# SCH_OnboardRobot_2024-01-02.net
KiCad netlist of a schematic drawn in EasyEDA
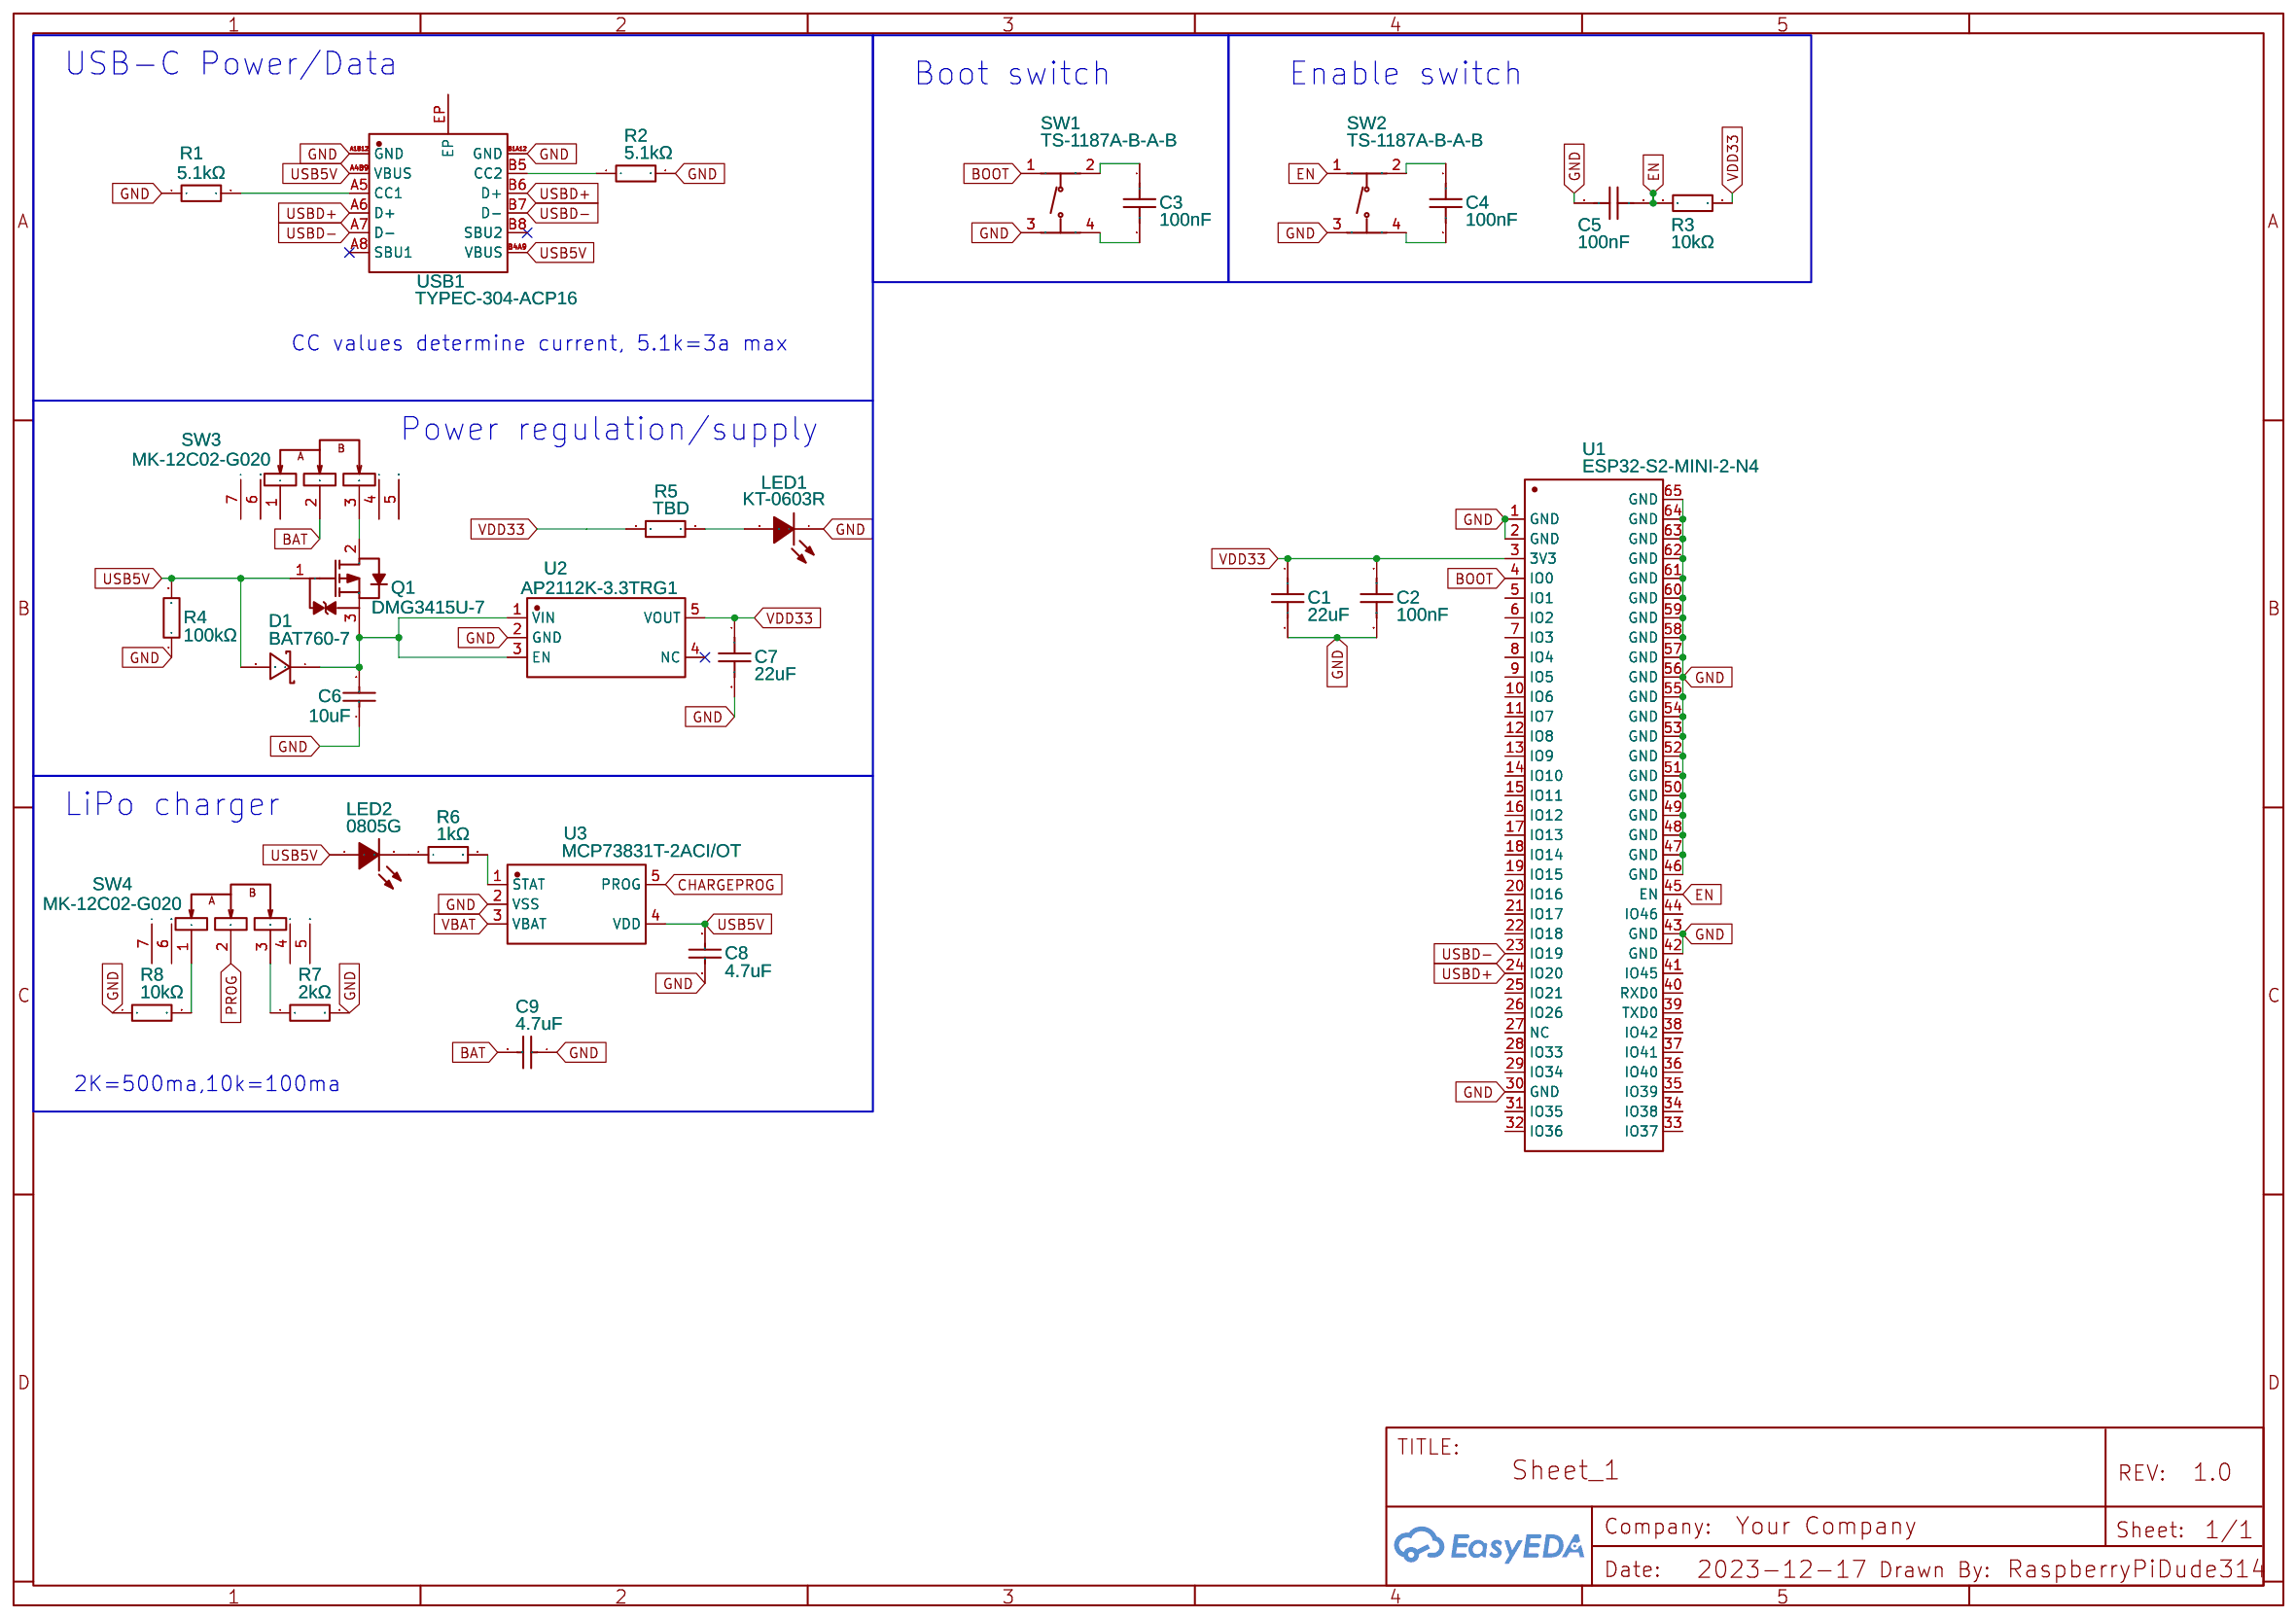
[diagram p0: schematic sheet]

(export (version "E")
  (design (tool "Eeschema 10.0.6"))
  (components
    (comp (ref "C1")
      (value "22uF")
      (fields
        (field (name "Manufacturer Part") "CL10A226MQ8NRNC")
        (field (name "Manufacturer") "SAMSUNG(三星)")
      )
      (libsource (lib "") (part "CL10A226MQ8NRNC"))
    )
    (comp (ref "C2")
      (value "100nF")
      (fields
        (field (name "Manufacturer Part") "CC0603KRX7R9BB104")
        (field (name "Manufacturer") "YAGEO(国巨)")
      )
      (libsource (lib "") (part "CC0603KRX7R9BB104_1"))
    )
    (comp (ref "C3")
      (value "100nF")
      (fields
        (field (name "Manufacturer Part") "CC0603KRX7R9BB104")
        (field (name "Manufacturer") "YAGEO(国巨)")
      )
      (libsource (lib "") (part "CC0603KRX7R9BB104_1"))
    )
    (comp (ref "C4")
      (value "100nF")
      (fields
        (field (name "Manufacturer Part") "CC0603KRX7R9BB104")
        (field (name "Manufacturer") "YAGEO(国巨)")
      )
      (libsource (lib "") (part "CC0603KRX7R9BB104_1"))
    )
    (comp (ref "C5")
      (value "100nF")
      (fields
        (field (name "Manufacturer Part") "CC0603KRX7R9BB104")
        (field (name "Manufacturer") "YAGEO(国巨)")
      )
      (libsource (lib "") (part "CC0603KRX7R9BB104"))
    )
    (comp (ref "C6")
      (value "10uF")
      (fields
        (field (name "Manufacturer Part") "CL21A106KAYNNNE")
        (field (name "Manufacturer") "SAMSUNG(三星)")
      )
      (libsource (lib "") (part "CL21A106KAYNNNE"))
    )
    (comp (ref "C7")
      (value "22uF")
      (fields
        (field (name "Manufacturer Part") "CL10A226MQ8NRNC")
        (field (name "Manufacturer") "SAMSUNG(三星)")
      )
      (libsource (lib "") (part "CL10A226MQ8NRNC"))
    )
    (comp (ref "C8")
      (value "4.7uF")
      (fields
        (field (name "Manufacturer Part") "CL05A475MP5NRNC")
        (field (name "Manufacturer") "SAMSUNG(三星)")
      )
      (libsource (lib "") (part "CL05A475MP5NRNC_1"))
    )
    (comp (ref "C9")
      (value "4.7uF")
      (fields
        (field (name "Manufacturer Part") "CL05A475MP5NRNC")
        (field (name "Manufacturer") "SAMSUNG(三星)")
      )
      (libsource (lib "") (part "CL05A475MP5NRNC"))
    )
    (comp (ref "D1")
      (value "BAT760-7")
      (fields (field (name "Manufacturer") "DIODES(美台)"))
      (libsource (lib "") (part "BAT760-7"))
    )
    (comp (ref "LED1")
      (value "KT-0603R")
      (fields (field (name "Manufacturer") "KENTO"))
      (libsource (lib "") (part "KT-0603R"))
    )
    (comp (ref "LED2")
      (value "0805G")
      (fields (field (name "Manufacturer Part") "KT-0805翠绿") (field (name "Manufacturer") "KENTO"))
      (libsource (lib "") (part "0805G (Green)"))
    )
    (comp (ref "Q1")
      (value "DMG3415U-7")
      (fields (field (name "Manufacturer") "DIODES(美台)"))
      (libsource (lib "") (part "DMG3415U-7"))
    )
    (comp (ref "R1")
      (value "5.1kΩ")
      (fields
        (field (name "Manufacturer Part") "0402WGF5101TCE")
        (field (name "Manufacturer") "UNI-ROYAL(厚声)")
      )
      (libsource (lib "") (part "0402WGF5101TCE"))
    )
    (comp (ref "R2")
      (value "5.1kΩ")
      (fields
        (field (name "Manufacturer Part") "0402WGF5101TCE")
        (field (name "Manufacturer") "UNI-ROYAL(厚声)")
      )
      (libsource (lib "") (part "0402WGF5101TCE"))
    )
    (comp (ref "R3")
      (value "10kΩ")
      (fields
        (field (name "Manufacturer Part") "0603WAF1002T5E")
        (field (name "Manufacturer") "UNI-ROYAL(厚声)")
      )
      (libsource (lib "") (part "0603WAF1002T5E"))
    )
    (comp (ref "R4")
      (value "100kΩ")
      (fields
        (field (name "Manufacturer Part") "1206W4F1003T5E")
        (field (name "Manufacturer") "UNI-ROYAL(厚声)")
      )
      (libsource (lib "") (part "1206W4F1003T5E"))
    )
    (comp (ref "R5") (value "TBD") (libsource (lib "") (part "0805 360 ohm Resistor")))
    (comp (ref "R6")
      (value "1kΩ")
      (fields
        (field (name "Manufacturer Part") "0805W8F1001T5E")
        (field (name "Manufacturer") "UNI-ROYAL(厚声)")
      )
      (libsource (lib "") (part "0805W8F1001T5E"))
    )
    (comp (ref "R7")
      (value "2kΩ")
      (fields
        (field (name "Manufacturer Part") "0603WAF2001T5E")
        (field (name "Manufacturer") "UNI-ROYAL(厚声)")
      )
      (libsource (lib "") (part "0603WAF2001T5E"))
    )
    (comp (ref "R8")
      (value "10kΩ")
      (fields
        (field (name "Manufacturer Part") "0805W8F1002T5E")
        (field (name "Manufacturer") "UNI-ROYAL(厚声)")
      )
      (libsource (lib "") (part "0805W8F1002T5E"))
    )
    (comp (ref "SW1")
      (value "TS-1187A-B-A-B")
      (fields (field (name "Manufacturer") "XKB Connectivity(中国星坤)"))
      (libsource (lib "") (part "TS-1187A-B-A-B"))
    )
    (comp (ref "SW2")
      (value "TS-1187A-B-A-B")
      (fields (field (name "Manufacturer") "XKB Connectivity(中国星坤)"))
      (libsource (lib "") (part "TS-1187A-B-A-B"))
    )
    (comp (ref "SW3")
      (value "MK-12C02-G020")
      (fields (field (name "Manufacturer") "G-Switch"))
      (libsource (lib "") (part "MK-12C02-G020"))
    )
    (comp (ref "SW4")
      (value "MK-12C02-G020")
      (fields (field (name "Manufacturer") "G-Switch"))
      (libsource (lib "") (part "MK-12C02-G020"))
    )
    (comp (ref "U1")
      (value "ESP32-S2-MINI-2-N4")
      (fields (field (name "Manufacturer") "ESPRESSIF(乐鑫)"))
      (libsource (lib "") (part "ESP32-S2-MINI-2-N4"))
    )
    (comp (ref "U2")
      (value "AP2112K-3.3TRG1")
      (fields (field (name "Manufacturer") "DIODES(美台)"))
      (libsource (lib "") (part "AP2112K-3.3TRG1"))
    )
    (comp (ref "U3")
      (value "MCP73831T-2ACI/OT")
      (fields (field (name "Manufacturer") "MICROCHIP(美国微芯)"))
      (libsource (lib "") (part "MCP73831T-2ACI/OT"))
    )
    (comp (ref "USB1")
      (value "TYPEC-304-ACP16")
      (fields (field (name "Manufacturer") "XUNPU(讯普)"))
      (libsource (lib "") (part "TYPEC-304-ACP16"))
    )
  )
  (nets
    (net (code "1") (name "BAT") (class "Default")
      (node (ref "C9") (pin "2") (pinfunction "2_2") (pintype "input"))
      (node (ref "SW3") (pin "2") (pinfunction "2_2") (pintype "unspecified"))
    )
    (net (code "2") (name "BOOT") (class "Default")
      (node (ref "SW1") (pin "1") (pinfunction "A_1") (pintype "unspecified"))
      (node (ref "U1") (pin "4") (pinfunction "IO0_4") (pintype "unspecified"))
    )
    (net (code "3") (name "CHARGEPROG") (class "Default")
      (node (ref "U3") (pin "5") (pinfunction "PROG_5") (pintype "unspecified"))
    )
    (net (code "4") (name "EN") (class "Default")
      (node (ref "C5") (pin "2") (pinfunction "2_2") (pintype "unspecified"))
      (node (ref "R3") (pin "2") (pinfunction "2_2") (pintype "input"))
      (node (ref "SW2") (pin "1") (pinfunction "A_1") (pintype "unspecified"))
      (node (ref "U1") (pin "45") (pinfunction "EN_45") (pintype "unspecified"))
    )
    (net (code "5") (name "GND") (class "Default")
      (node (ref "C1") (pin "2") (pinfunction "2_2") (pintype "unspecified"))
      (node (ref "C2") (pin "2") (pinfunction "2_2") (pintype "unspecified"))
      (node (ref "C5") (pin "1") (pinfunction "1_1") (pintype "unspecified"))
      (node (ref "C6") (pin "1") (pinfunction "1_1") (pintype "input"))
      (node (ref "C7") (pin "2") (pinfunction "2_2") (pintype "unspecified"))
      (node (ref "C8") (pin "1") (pinfunction "1_1") (pintype "input"))
      (node (ref "C9") (pin "1") (pinfunction "1_1") (pintype "input"))
      (node (ref "LED1") (pin "1") (pinfunction "K_1") (pintype "unspecified"))
      (node (ref "R1") (pin "1") (pinfunction "1_1") (pintype "input"))
      (node (ref "R2") (pin "2") (pinfunction "2_2") (pintype "input"))
      (node (ref "R4") (pin "1") (pinfunction "1_1") (pintype "input"))
      (node (ref "R7") (pin "2") (pinfunction "2_2") (pintype "input"))
      (node (ref "R8") (pin "1") (pinfunction "1_1") (pintype "input"))
      (node (ref "SW1") (pin "3") (pinfunction "C_3") (pintype "unspecified"))
      (node (ref "SW2") (pin "3") (pinfunction "C_3") (pintype "unspecified"))
      (node (ref "U1") (pin "1") (pinfunction "GND_1") (pintype "unspecified"))
      (node (ref "U1") (pin "2") (pinfunction "GND_2") (pintype "unspecified"))
      (node (ref "U1") (pin "30") (pinfunction "GND_30") (pintype "unspecified"))
      (node (ref "U1") (pin "42") (pinfunction "GND_42") (pintype "unspecified"))
      (node (ref "U1") (pin "43") (pinfunction "GND_43") (pintype "unspecified"))
      (node (ref "U1") (pin "46") (pinfunction "GND_46") (pintype "unspecified"))
      (node (ref "U1") (pin "47") (pinfunction "GND_47") (pintype "unspecified"))
      (node (ref "U1") (pin "48") (pinfunction "GND_48") (pintype "unspecified"))
      (node (ref "U1") (pin "49") (pinfunction "GND_49") (pintype "unspecified"))
      (node (ref "U1") (pin "50") (pinfunction "GND_50") (pintype "unspecified"))
      (node (ref "U1") (pin "51") (pinfunction "GND_51") (pintype "unspecified"))
      (node (ref "U1") (pin "52") (pinfunction "GND_52") (pintype "unspecified"))
      (node (ref "U1") (pin "53") (pinfunction "GND_53") (pintype "unspecified"))
      (node (ref "U1") (pin "54") (pinfunction "GND_54") (pintype "unspecified"))
      (node (ref "U1") (pin "55") (pinfunction "GND_55") (pintype "unspecified"))
      (node (ref "U1") (pin "56") (pinfunction "GND_56") (pintype "unspecified"))
      (node (ref "U1") (pin "57") (pinfunction "GND_57") (pintype "unspecified"))
      (node (ref "U1") (pin "58") (pinfunction "GND_58") (pintype "unspecified"))
      (node (ref "U1") (pin "59") (pinfunction "GND_59") (pintype "unspecified"))
      (node (ref "U1") (pin "60") (pinfunction "GND_60") (pintype "unspecified"))
      (node (ref "U1") (pin "61") (pinfunction "GND_61") (pintype "unspecified"))
      (node (ref "U1") (pin "62") (pinfunction "GND_62") (pintype "unspecified"))
      (node (ref "U1") (pin "63") (pinfunction "GND_63") (pintype "unspecified"))
      (node (ref "U1") (pin "64") (pinfunction "GND_64") (pintype "unspecified"))
      (node (ref "U1") (pin "65") (pinfunction "GND_65") (pintype "unspecified"))
      (node (ref "U2") (pin "2") (pinfunction "GND_2") (pintype "unspecified"))
      (node (ref "U3") (pin "2") (pinfunction "VSS_2") (pintype "unspecified"))
      (node (ref "USB1") (pin "A1B12") (pinfunction "GND_A1B12") (pintype "unspecified"))
      (node (ref "USB1") (pin "B1A12") (pinfunction "GND_B1A12") (pintype "unspecified"))
    )
    (net (code "6") (name "Net-(LED1-A)") (class "Default")
      (node (ref "LED1") (pin "2") (pinfunction "A_2") (pintype "unspecified"))
      (node (ref "R5") (pin "2") (pinfunction "2_2") (pintype "unspecified"))
    )
    (net (code "7") (name "Net-(LED2-K)") (class "Default")
      (node (ref "LED2") (pin "2") (pinfunction "K_2") (pintype "unspecified"))
      (node (ref "R6") (pin "1") (pinfunction "1_1") (pintype "input"))
    )
    (net (code "8") (name "Net-(Q1-D)") (class "Default")
      (node (ref "Q1") (pin "2") (pinfunction "D_2") (pintype "unspecified"))
      (node (ref "SW3") (pin "3") (pinfunction "3_3") (pintype "unspecified"))
    )
    (net (code "9") (name "Net-(Q1-S)") (class "Default")
      (node (ref "C6") (pin "2") (pinfunction "2_2") (pintype "input"))
      (node (ref "D1") (pin "1") (pinfunction "1_1") (pintype "unspecified"))
      (node (ref "Q1") (pin "3") (pinfunction "S_3") (pintype "unspecified"))
      (node (ref "U2") (pin "1") (pinfunction "VIN_1") (pintype "unspecified"))
      (node (ref "U2") (pin "3") (pinfunction "EN_3") (pintype "unspecified"))
    )
    (net (code "10") (name "Net-(R7-Pad1)") (class "Default")
      (node (ref "R7") (pin "1") (pinfunction "1_1") (pintype "input"))
      (node (ref "SW4") (pin "3") (pinfunction "3_3") (pintype "unspecified"))
    )
    (net (code "11") (name "Net-(R8-Pad2)") (class "Default")
      (node (ref "R8") (pin "2") (pinfunction "2_2") (pintype "input"))
      (node (ref "SW4") (pin "1") (pinfunction "1_1") (pintype "unspecified"))
    )
    (net (code "12") (name "Net-(SW1-B)") (class "Default")
      (node (ref "C3") (pin "1") (pinfunction "1_1") (pintype "unspecified"))
      (node (ref "SW1") (pin "2") (pinfunction "B_2") (pintype "unspecified"))
    )
    (net (code "13") (name "Net-(SW1-D)") (class "Default")
      (node (ref "C3") (pin "2") (pinfunction "2_2") (pintype "unspecified"))
      (node (ref "SW1") (pin "4") (pinfunction "D_4") (pintype "unspecified"))
    )
    (net (code "14") (name "Net-(SW2-B)") (class "Default")
      (node (ref "C4") (pin "1") (pinfunction "1_1") (pintype "unspecified"))
      (node (ref "SW2") (pin "2") (pinfunction "B_2") (pintype "unspecified"))
    )
    (net (code "15") (name "Net-(SW2-D)") (class "Default")
      (node (ref "C4") (pin "2") (pinfunction "2_2") (pintype "unspecified"))
      (node (ref "SW2") (pin "4") (pinfunction "D_4") (pintype "unspecified"))
    )
    (net (code "16") (name "Net-(U3-STAT)") (class "Default")
      (node (ref "R6") (pin "2") (pinfunction "2_2") (pintype "input"))
      (node (ref "U3") (pin "1") (pinfunction "STAT_1") (pintype "unspecified"))
    )
    (net (code "17") (name "Net-(USB1-CC1)") (class "Default")
      (node (ref "R1") (pin "2") (pinfunction "2_2") (pintype "input"))
      (node (ref "USB1") (pin "A5") (pinfunction "CC1_A5") (pintype "unspecified"))
    )
    (net (code "18") (name "Net-(USB1-CC2)") (class "Default")
      (node (ref "R2") (pin "1") (pinfunction "1_1") (pintype "input"))
      (node (ref "USB1") (pin "B5") (pinfunction "CC2_B5") (pintype "unspecified"))
    )
    (net (code "19") (name "PROG") (class "Default")
      (node (ref "SW4") (pin "2") (pinfunction "2_2") (pintype "unspecified"))
    )
    (net (code "20") (name "USB5V") (class "Default")
      (node (ref "C8") (pin "2") (pinfunction "2_2") (pintype "input"))
      (node (ref "D1") (pin "2") (pinfunction "2_2") (pintype "unspecified"))
      (node (ref "LED2") (pin "1") (pinfunction "A_1") (pintype "unspecified"))
      (node (ref "Q1") (pin "1") (pinfunction "G_1") (pintype "unspecified"))
      (node (ref "R4") (pin "2") (pinfunction "2_2") (pintype "input"))
      (node (ref "U3") (pin "4") (pinfunction "VDD_4") (pintype "unspecified"))
      (node (ref "USB1") (pin "A4B9") (pinfunction "VBUS_A4B9") (pintype "unspecified"))
      (node (ref "USB1") (pin "B4A9") (pinfunction "VBUS_B4A9") (pintype "unspecified"))
    )
    (net (code "21") (name "USBD+") (class "Default")
      (node (ref "U1") (pin "24") (pinfunction "IO20_24") (pintype "unspecified"))
      (node (ref "USB1") (pin "A6") (pinfunction "D+_A6") (pintype "unspecified"))
      (node (ref "USB1") (pin "B6") (pinfunction "D+_B6") (pintype "unspecified"))
    )
    (net (code "22") (name "USBD-") (class "Default")
      (node (ref "U1") (pin "23") (pinfunction "IO19_23") (pintype "unspecified"))
      (node (ref "USB1") (pin "A7") (pinfunction "D-_A7") (pintype "unspecified"))
      (node (ref "USB1") (pin "B7") (pinfunction "D-_B7") (pintype "unspecified"))
    )
    (net (code "23") (name "VBAT") (class "Default")
      (node (ref "U3") (pin "3") (pinfunction "VBAT_3") (pintype "unspecified"))
    )
    (net (code "24") (name "VDD33") (class "Default")
      (node (ref "C1") (pin "1") (pinfunction "1_1") (pintype "unspecified"))
      (node (ref "C2") (pin "1") (pinfunction "1_1") (pintype "unspecified"))
      (node (ref "C7") (pin "1") (pinfunction "1_1") (pintype "unspecified"))
      (node (ref "R3") (pin "1") (pinfunction "1_1") (pintype "input"))
      (node (ref "R5") (pin "1") (pinfunction "1_1") (pintype "unspecified"))
      (node (ref "U1") (pin "3") (pinfunction "3V3_3") (pintype "unspecified"))
      (node (ref "U2") (pin "5") (pinfunction "VOUT_5") (pintype "unspecified"))
    )
    (net (code "25") (name "unconnected-(SW3-Pad1)") (class "Default")
      (node (ref "SW3") (pin "1") (pinfunction "1_1") (pintype "unspecified"))
    )
    (net (code "26") (name "unconnected-(SW3-Pad4)") (class "Default")
      (node (ref "SW3") (pin "4") (pinfunction "4_4") (pintype "unspecified"))
    )
    (net (code "27") (name "unconnected-(SW3-Pad5)") (class "Default")
      (node (ref "SW3") (pin "5") (pinfunction "5_5") (pintype "unspecified"))
    )
    (net (code "28") (name "unconnected-(SW3-Pad6)") (class "Default")
      (node (ref "SW3") (pin "6") (pinfunction "6_6") (pintype "unspecified"))
    )
    (net (code "29") (name "unconnected-(SW3-Pad7)") (class "Default")
      (node (ref "SW3") (pin "7") (pinfunction "7_7") (pintype "unspecified"))
    )
    (net (code "30") (name "unconnected-(SW4-Pad4)") (class "Default")
      (node (ref "SW4") (pin "4") (pinfunction "4_4") (pintype "unspecified"))
    )
    (net (code "31") (name "unconnected-(SW4-Pad5)") (class "Default")
      (node (ref "SW4") (pin "5") (pinfunction "5_5") (pintype "unspecified"))
    )
    (net (code "32") (name "unconnected-(SW4-Pad6)") (class "Default")
      (node (ref "SW4") (pin "6") (pinfunction "6_6") (pintype "unspecified"))
    )
    (net (code "33") (name "unconnected-(SW4-Pad7)") (class "Default")
      (node (ref "SW4") (pin "7") (pinfunction "7_7") (pintype "unspecified"))
    )
    (net (code "34") (name "unconnected-(U1-IO1-Pad5)") (class "Default")
      (node (ref "U1") (pin "5") (pinfunction "IO1_5") (pintype "unspecified"))
    )
    (net (code "35") (name "unconnected-(U1-IO2-Pad6)") (class "Default")
      (node (ref "U1") (pin "6") (pinfunction "IO2_6") (pintype "unspecified"))
    )
    (net (code "36") (name "unconnected-(U1-IO3-Pad7)") (class "Default")
      (node (ref "U1") (pin "7") (pinfunction "IO3_7") (pintype "unspecified"))
    )
    (net (code "37") (name "unconnected-(U1-IO4-Pad8)") (class "Default")
      (node (ref "U1") (pin "8") (pinfunction "IO4_8") (pintype "unspecified"))
    )
    (net (code "38") (name "unconnected-(U1-IO5-Pad9)") (class "Default")
      (node (ref "U1") (pin "9") (pinfunction "IO5_9") (pintype "unspecified"))
    )
    (net (code "39") (name "unconnected-(U1-IO6-Pad10)") (class "Default")
      (node (ref "U1") (pin "10") (pinfunction "IO6_10") (pintype "unspecified"))
    )
    (net (code "40") (name "unconnected-(U1-IO7-Pad11)") (class "Default")
      (node (ref "U1") (pin "11") (pinfunction "IO7_11") (pintype "unspecified"))
    )
    (net (code "41") (name "unconnected-(U1-IO8-Pad12)") (class "Default")
      (node (ref "U1") (pin "12") (pinfunction "IO8_12") (pintype "unspecified"))
    )
    (net (code "42") (name "unconnected-(U1-IO9-Pad13)") (class "Default")
      (node (ref "U1") (pin "13") (pinfunction "IO9_13") (pintype "unspecified"))
    )
    (net (code "43") (name "unconnected-(U1-IO10-Pad14)") (class "Default")
      (node (ref "U1") (pin "14") (pinfunction "IO10_14") (pintype "unspecified"))
    )
    (net (code "44") (name "unconnected-(U1-IO11-Pad15)") (class "Default")
      (node (ref "U1") (pin "15") (pinfunction "IO11_15") (pintype "unspecified"))
    )
    (net (code "45") (name "unconnected-(U1-IO12-Pad16)") (class "Default")
      (node (ref "U1") (pin "16") (pinfunction "IO12_16") (pintype "unspecified"))
    )
    (net (code "46") (name "unconnected-(U1-IO13-Pad17)") (class "Default")
      (node (ref "U1") (pin "17") (pinfunction "IO13_17") (pintype "unspecified"))
    )
    (net (code "47") (name "unconnected-(U1-IO14-Pad18)") (class "Default")
      (node (ref "U1") (pin "18") (pinfunction "IO14_18") (pintype "unspecified"))
    )
    (net (code "48") (name "unconnected-(U1-IO15-Pad19)") (class "Default")
      (node (ref "U1") (pin "19") (pinfunction "IO15_19") (pintype "unspecified"))
    )
    (net (code "49") (name "unconnected-(U1-IO16-Pad20)") (class "Default")
      (node (ref "U1") (pin "20") (pinfunction "IO16_20") (pintype "unspecified"))
    )
    (net (code "50") (name "unconnected-(U1-IO17-Pad21)") (class "Default")
      (node (ref "U1") (pin "21") (pinfunction "IO17_21") (pintype "unspecified"))
    )
    (net (code "51") (name "unconnected-(U1-IO18-Pad22)") (class "Default")
      (node (ref "U1") (pin "22") (pinfunction "IO18_22") (pintype "unspecified"))
    )
    (net (code "52") (name "unconnected-(U1-IO21-Pad25)") (class "Default")
      (node (ref "U1") (pin "25") (pinfunction "IO21_25") (pintype "unspecified"))
    )
    (net (code "53") (name "unconnected-(U1-IO26-Pad26)") (class "Default")
      (node (ref "U1") (pin "26") (pinfunction "IO26_26") (pintype "unspecified"))
    )
    (net (code "54") (name "unconnected-(U1-IO33-Pad28)") (class "Default")
      (node (ref "U1") (pin "28") (pinfunction "IO33_28") (pintype "unspecified"))
    )
    (net (code "55") (name "unconnected-(U1-IO34-Pad29)") (class "Default")
      (node (ref "U1") (pin "29") (pinfunction "IO34_29") (pintype "unspecified"))
    )
    (net (code "56") (name "unconnected-(U1-IO35-Pad31)") (class "Default")
      (node (ref "U1") (pin "31") (pinfunction "IO35_31") (pintype "unspecified"))
    )
    (net (code "57") (name "unconnected-(U1-IO36-Pad32)") (class "Default")
      (node (ref "U1") (pin "32") (pinfunction "IO36_32") (pintype "unspecified"))
    )
    (net (code "58") (name "unconnected-(U1-IO37-Pad33)") (class "Default")
      (node (ref "U1") (pin "33") (pinfunction "IO37_33") (pintype "unspecified"))
    )
    (net (code "59") (name "unconnected-(U1-IO38-Pad34)") (class "Default")
      (node (ref "U1") (pin "34") (pinfunction "IO38_34") (pintype "unspecified"))
    )
    (net (code "60") (name "unconnected-(U1-IO39-Pad35)") (class "Default")
      (node (ref "U1") (pin "35") (pinfunction "IO39_35") (pintype "unspecified"))
    )
    (net (code "61") (name "unconnected-(U1-IO40-Pad36)") (class "Default")
      (node (ref "U1") (pin "36") (pinfunction "IO40_36") (pintype "unspecified"))
    )
    (net (code "62") (name "unconnected-(U1-IO41-Pad37)") (class "Default")
      (node (ref "U1") (pin "37") (pinfunction "IO41_37") (pintype "unspecified"))
    )
    (net (code "63") (name "unconnected-(U1-IO42-Pad38)") (class "Default")
      (node (ref "U1") (pin "38") (pinfunction "IO42_38") (pintype "unspecified"))
    )
    (net (code "64") (name "unconnected-(U1-IO45-Pad41)") (class "Default")
      (node (ref "U1") (pin "41") (pinfunction "IO45_41") (pintype "unspecified"))
    )
    (net (code "65") (name "unconnected-(U1-IO46-Pad44)") (class "Default")
      (node (ref "U1") (pin "44") (pinfunction "IO46_44") (pintype "unspecified"))
    )
    (net (code "66") (name "unconnected-(U1-NC-Pad27)") (class "Default")
      (node (ref "U1") (pin "27") (pinfunction "NC_27") (pintype "unspecified"))
    )
    (net (code "67") (name "unconnected-(U1-RXD0-Pad40)") (class "Default")
      (node (ref "U1") (pin "40") (pinfunction "RXD0_40") (pintype "unspecified"))
    )
    (net (code "68") (name "unconnected-(U1-TXD0-Pad39)") (class "Default")
      (node (ref "U1") (pin "39") (pinfunction "TXD0_39") (pintype "unspecified"))
    )
    (net (code "69") (name "unconnected-(U2-NC-Pad4)") (class "Default")
      (node (ref "U2") (pin "4") (pinfunction "NC_4") (pintype "unspecified+no_connect"))
    )
    (net (code "70") (name "unconnected-(USB1-PadEP)") (class "Default")
      (node (ref "USB1") (pin "EP") (pinfunction "EP_EP") (pintype "unspecified"))
    )
    (net (code "71") (name "unconnected-(USB1-SBU1-PadA8)") (class "Default")
      (node (ref "USB1") (pin "A8") (pinfunction "SBU1_A8") (pintype "unspecified+no_connect"))
    )
    (net (code "72") (name "unconnected-(USB1-SBU2-PadB8)") (class "Default")
      (node (ref "USB1") (pin "B8") (pinfunction "SBU2_B8") (pintype "unspecified+no_connect"))
    )
  )
)
